# SCH_NFC-Card-Saumshar_2024-10-10.net
KiCad netlist of a schematic drawn in EasyEDA
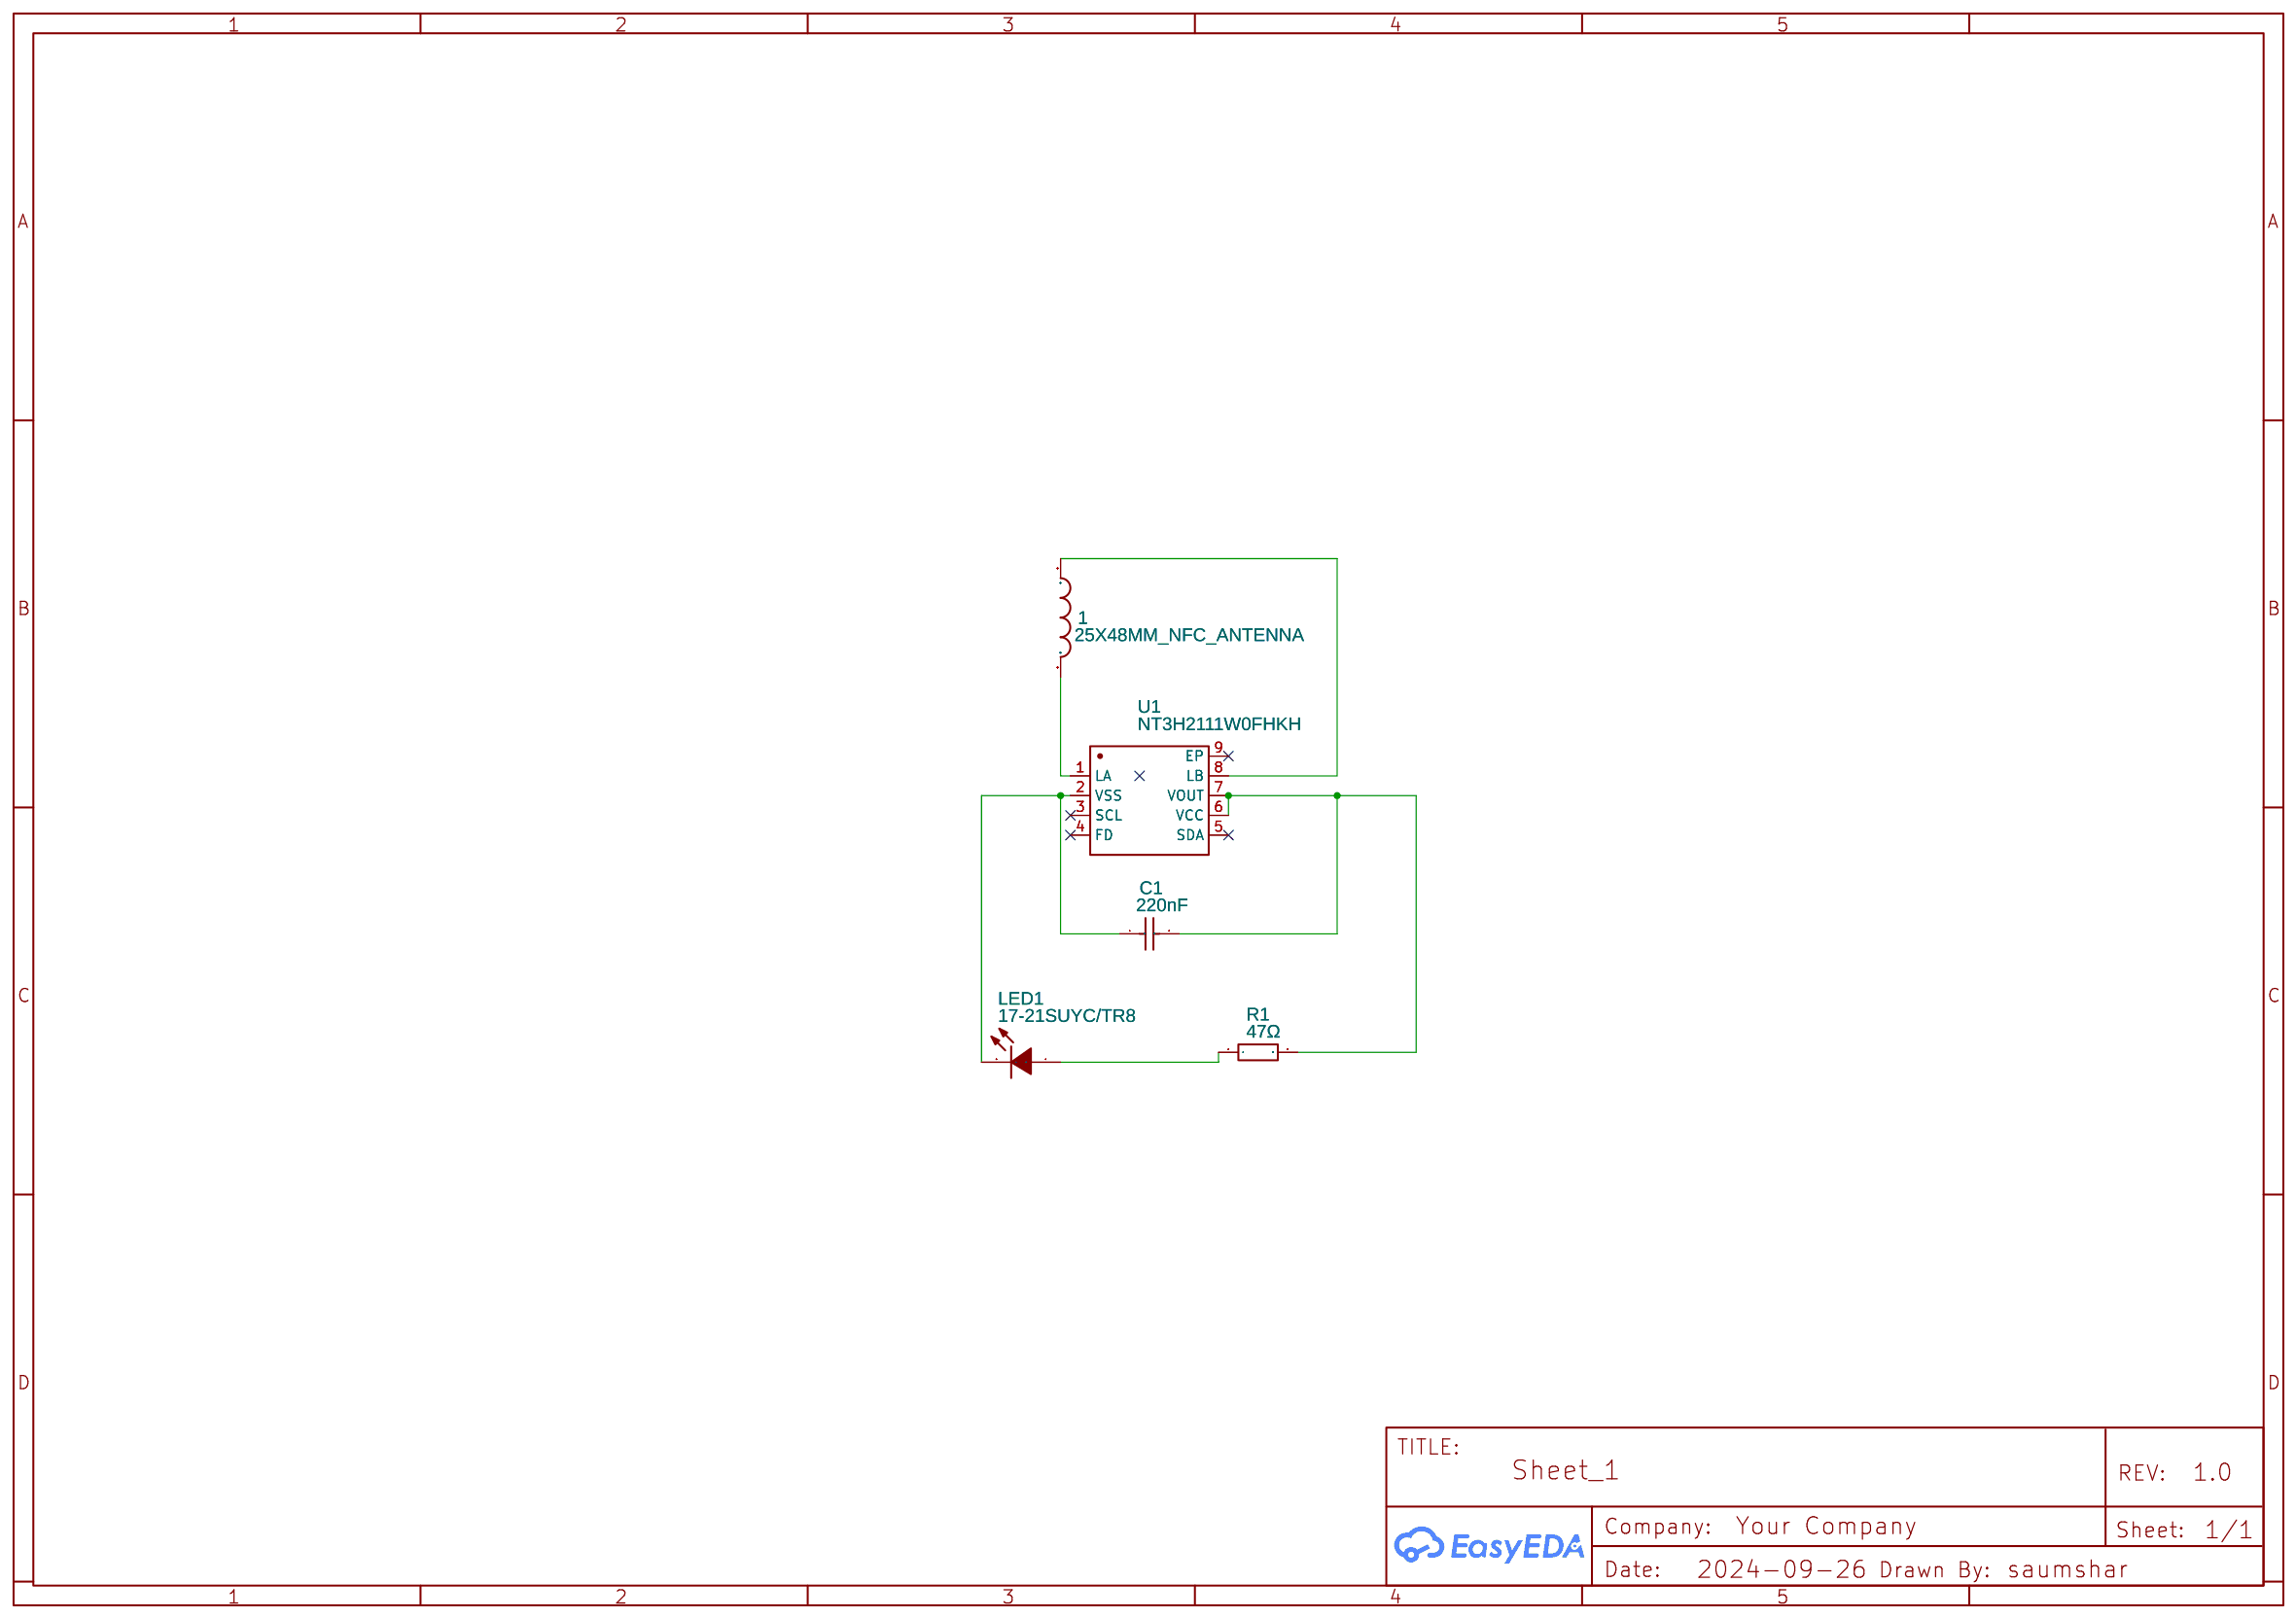
[diagram p0: schematic sheet]

(export (version "E")
  (design (tool "Eeschema 10.0.6"))
  (components
    (comp (ref "1") (value "25X48MM_NFC_ANTENNA") (libsource (lib "") (part "25X48MM_NFC_ANTENNA")))
    (comp (ref "C1")
      (value "220nF")
      (fields
        (field (name "Manufacturer Part") "CL10B224KA8NNNC")
        (field (name "Manufacturer") "SAMSUNG(三星)")
      )
      (libsource (lib "") (part "CL10B224KA8NNNC"))
    )
    (comp (ref "LED1")
      (value "17-21SUYC/TR8")
      (fields (field (name "Manufacturer Part") "KT-0805黄灯") (field (name "Manufacturer") "KENTO"))
      (libsource (lib "") (part "17-21SUYC/TR8"))
    )
    (comp (ref "R1")
      (value "47Ω")
      (fields
        (field (name "Manufacturer Part") "0603WAF470JT5E")
        (field (name "Manufacturer") "UNI-ROYAL(厚声)")
      )
      (libsource (lib "") (part "0603WAF470JT5E"))
    )
    (comp (ref "U1")
      (value "NT3H2111W0FHKH")
      (fields (field (name "Manufacturer") "NXP(恩智浦)"))
      (libsource (lib "") (part "NT3H2111W0FHKH"))
    )
  )
  (nets
    (net (code "1") (name "Net-(LED1-+)") (class "Default")
      (node (ref "LED1") (pin "1") (pinfunction "+_1") (pintype "unspecified"))
      (node (ref "R1") (pin "1") (pinfunction "1_1") (pintype "input"))
    )
    (net (code "2") (name "Net-(LED1--)") (class "Default")
      (node (ref "C1") (pin "1") (pinfunction "1_1") (pintype "input"))
      (node (ref "LED1") (pin "2") (pinfunction "-_2") (pintype "unspecified"))
      (node (ref "U1") (pin "2") (pinfunction "VSS_2") (pintype "unspecified"))
    )
    (net (code "3") (name "Net-(U1-LA)") (class "Default")
      (node (ref "1") (pin "P$2") (pinfunction "P$2_P$2") (pintype "bidirectional"))
      (node (ref "U1") (pin "1") (pinfunction "LA_1") (pintype "unspecified"))
    )
    (net (code "4") (name "Net-(U1-LB)") (class "Default")
      (node (ref "1") (pin "P$1") (pinfunction "P$1_P$1") (pintype "bidirectional"))
      (node (ref "U1") (pin "8") (pinfunction "LB_8") (pintype "unspecified"))
    )
    (net (code "5") (name "Net-(U1-VCC)") (class "Default")
      (node (ref "C1") (pin "2") (pinfunction "2_2") (pintype "input"))
      (node (ref "R1") (pin "2") (pinfunction "2_2") (pintype "input"))
      (node (ref "U1") (pin "6") (pinfunction "VCC_6") (pintype "unspecified"))
      (node (ref "U1") (pin "7") (pinfunction "VOUT_7") (pintype "unspecified"))
    )
    (net (code "6") (name "unconnected-(U1-EP-Pad9)") (class "Default")
      (node (ref "U1") (pin "9") (pinfunction "EP_9") (pintype "unspecified+no_connect"))
    )
    (net (code "7") (name "unconnected-(U1-FD-Pad4)") (class "Default")
      (node (ref "U1") (pin "4") (pinfunction "FD_4") (pintype "unspecified+no_connect"))
    )
    (net (code "8") (name "unconnected-(U1-SCL-Pad3)") (class "Default")
      (node (ref "U1") (pin "3") (pinfunction "SCL_3") (pintype "unspecified+no_connect"))
    )
    (net (code "9") (name "unconnected-(U1-SDA-Pad5)") (class "Default")
      (node (ref "U1") (pin "5") (pinfunction "SDA_5") (pintype "unspecified+no_connect"))
    )
  )
)
